# rgbled.net
KiCad netlist of a schematic drawn in EAGLE
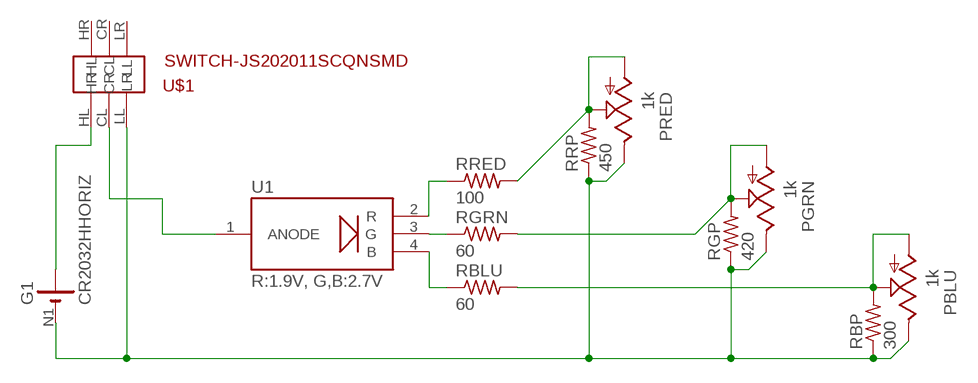
[diagram p0: schematic, sheet 1]

(export (version "E")
  (design (tool "Eeschema 10.0.6"))
  (components
    (comp (ref "G1")
      (value "CR2032HHORIZ")
      (footprint "eagle-import:LINX-BAT-HLD-001")
      (libsource (lib "eagle-import") (part "CR2032HHORIZ"))
    )
    (comp (ref "PBLU")
      (value "1k")
      (footprint "eagle-import:PTV111-1")
      (libsource (lib "eagle-import") (part "TRIM_US-PTV111-1"))
    )
    (comp (ref "PGRN")
      (value "1k")
      (footprint "eagle-import:PTV111-1")
      (libsource (lib "eagle-import") (part "TRIM_US-PTV111-1"))
    )
    (comp (ref "PRED")
      (value "1k")
      (footprint "eagle-import:PTV111-1")
      (libsource (lib "eagle-import") (part "TRIM_US-PTV111-1"))
    )
    (comp (ref "RBLU")
      (value "60")
      (footprint "eagle-import:M0805")
      (libsource (lib "eagle-import") (part "resistor_R-US_M0805"))
    )
    (comp (ref "RBP")
      (value "300")
      (footprint "eagle-import:R0805")
      (libsource (lib "eagle-import") (part "R-US_R0805"))
    )
    (comp (ref "RGP")
      (value "420")
      (footprint "eagle-import:R0805")
      (libsource (lib "eagle-import") (part "R-US_R0805"))
    )
    (comp (ref "RGRN")
      (value "60")
      (footprint "eagle-import:M0805")
      (libsource (lib "eagle-import") (part "resistor_R-US_M0805"))
    )
    (comp (ref "RRED")
      (value "100")
      (footprint "eagle-import:M0805")
      (libsource (lib "eagle-import") (part "resistor_R-US_M0805"))
    )
    (comp (ref "RRP")
      (value "450")
      (footprint "eagle-import:R0805")
      (libsource (lib "eagle-import") (part "R-US_R0805"))
    )
    (comp (ref "U$1")
      (value "SWITCH-JS202011SCQNSMD")
      (footprint "eagle-import:SWITCH-JS202011CQN")
      (libsource (lib "eagle-import") (part "SWITCH-JS202011SCQNSMD"))
    )
    (comp (ref "U1")
      (value "R:1.9V, G,B:2.7V")
      (footprint "eagle-import:LRTB_R48G")
      (libsource (lib "eagle-import") (part "LRTB_R48GSMD"))
    )
  )
  (nets
    (net (code "1") (name "Net-(G1-+-PadP@1)") (class "Default")
      (node (ref "G1") (pin "P@1") (pinfunction "+_P@1") (pintype "passive"))
      (node (ref "G1") (pin "P@2") (pinfunction "+_P@2") (pintype "passive"))
      (node (ref "U$1") (pin "HL") (pinfunction "HL_HL") (pintype "bidirectional"))
    )
    (net (code "2") (name "Net-(G1--)") (class "Default")
      (node (ref "G1") (pin "N1") (pinfunction "-_N1") (pintype "passive"))
      (node (ref "PBLU") (pin "1") (pinfunction "E_1") (pintype "passive"))
      (node (ref "PGRN") (pin "1") (pinfunction "E_1") (pintype "passive"))
      (node (ref "PRED") (pin "1") (pinfunction "E_1") (pintype "passive"))
      (node (ref "RBP") (pin "1") (pinfunction "1_1") (pintype "passive"))
      (node (ref "RGP") (pin "1") (pinfunction "1_1") (pintype "passive"))
      (node (ref "RRP") (pin "1") (pinfunction "1_1") (pintype "passive"))
      (node (ref "U$1") (pin "LL") (pinfunction "LL_LL") (pintype "bidirectional"))
    )
    (net (code "3") (name "Net-(PBLU-A)") (class "Default")
      (node (ref "PBLU") (pin "2") (pinfunction "S_2") (pintype "passive"))
      (node (ref "PBLU") (pin "3") (pinfunction "A_3") (pintype "passive"))
      (node (ref "RBLU") (pin "2") (pinfunction "2_2") (pintype "passive"))
      (node (ref "RBP") (pin "2") (pinfunction "2_2") (pintype "passive"))
    )
    (net (code "4") (name "Net-(PGRN-A)") (class "Default")
      (node (ref "PGRN") (pin "2") (pinfunction "S_2") (pintype "passive"))
      (node (ref "PGRN") (pin "3") (pinfunction "A_3") (pintype "passive"))
      (node (ref "RGP") (pin "2") (pinfunction "2_2") (pintype "passive"))
      (node (ref "RGRN") (pin "2") (pinfunction "2_2") (pintype "passive"))
    )
    (net (code "5") (name "Net-(PRED-A)") (class "Default")
      (node (ref "PRED") (pin "2") (pinfunction "S_2") (pintype "passive"))
      (node (ref "PRED") (pin "3") (pinfunction "A_3") (pintype "passive"))
      (node (ref "RRED") (pin "2") (pinfunction "2_2") (pintype "passive"))
      (node (ref "RRP") (pin "2") (pinfunction "2_2") (pintype "passive"))
    )
    (net (code "6") (name "Net-(U1-ANODE)") (class "Default")
      (node (ref "U$1") (pin "CL") (pinfunction "CL_CL") (pintype "bidirectional"))
      (node (ref "U1") (pin "1") (pinfunction "ANODE_1") (pintype "bidirectional"))
    )
    (net (code "7") (name "Net-(U1-B)") (class "Default")
      (node (ref "RBLU") (pin "1") (pinfunction "1_1") (pintype "passive"))
      (node (ref "U1") (pin "4") (pinfunction "B_4") (pintype "bidirectional"))
    )
    (net (code "8") (name "Net-(U1-G)") (class "Default")
      (node (ref "RGRN") (pin "1") (pinfunction "1_1") (pintype "passive"))
      (node (ref "U1") (pin "3") (pinfunction "G_3") (pintype "bidirectional"))
    )
    (net (code "9") (name "Net-(U1-R)") (class "Default")
      (node (ref "RRED") (pin "1") (pinfunction "1_1") (pintype "passive"))
      (node (ref "U1") (pin "2") (pinfunction "R_2") (pintype "bidirectional"))
    )
    (net (code "10") (name "unconnected-(U$1-PadCR)") (class "Default")
      (node (ref "U$1") (pin "CR") (pinfunction "CR_CR") (pintype "bidirectional"))
    )
    (net (code "11") (name "unconnected-(U$1-PadHR)") (class "Default")
      (node (ref "U$1") (pin "HR") (pinfunction "HR_HR") (pintype "bidirectional"))
    )
    (net (code "12") (name "unconnected-(U$1-PadLR)") (class "Default")
      (node (ref "U$1") (pin "LR") (pinfunction "LR_LR") (pintype "bidirectional"))
    )
  )
)
